# New_Project_2025-05-17_15-31-49.net
KiCad netlist of a schematic drawn in EasyEDA Pro
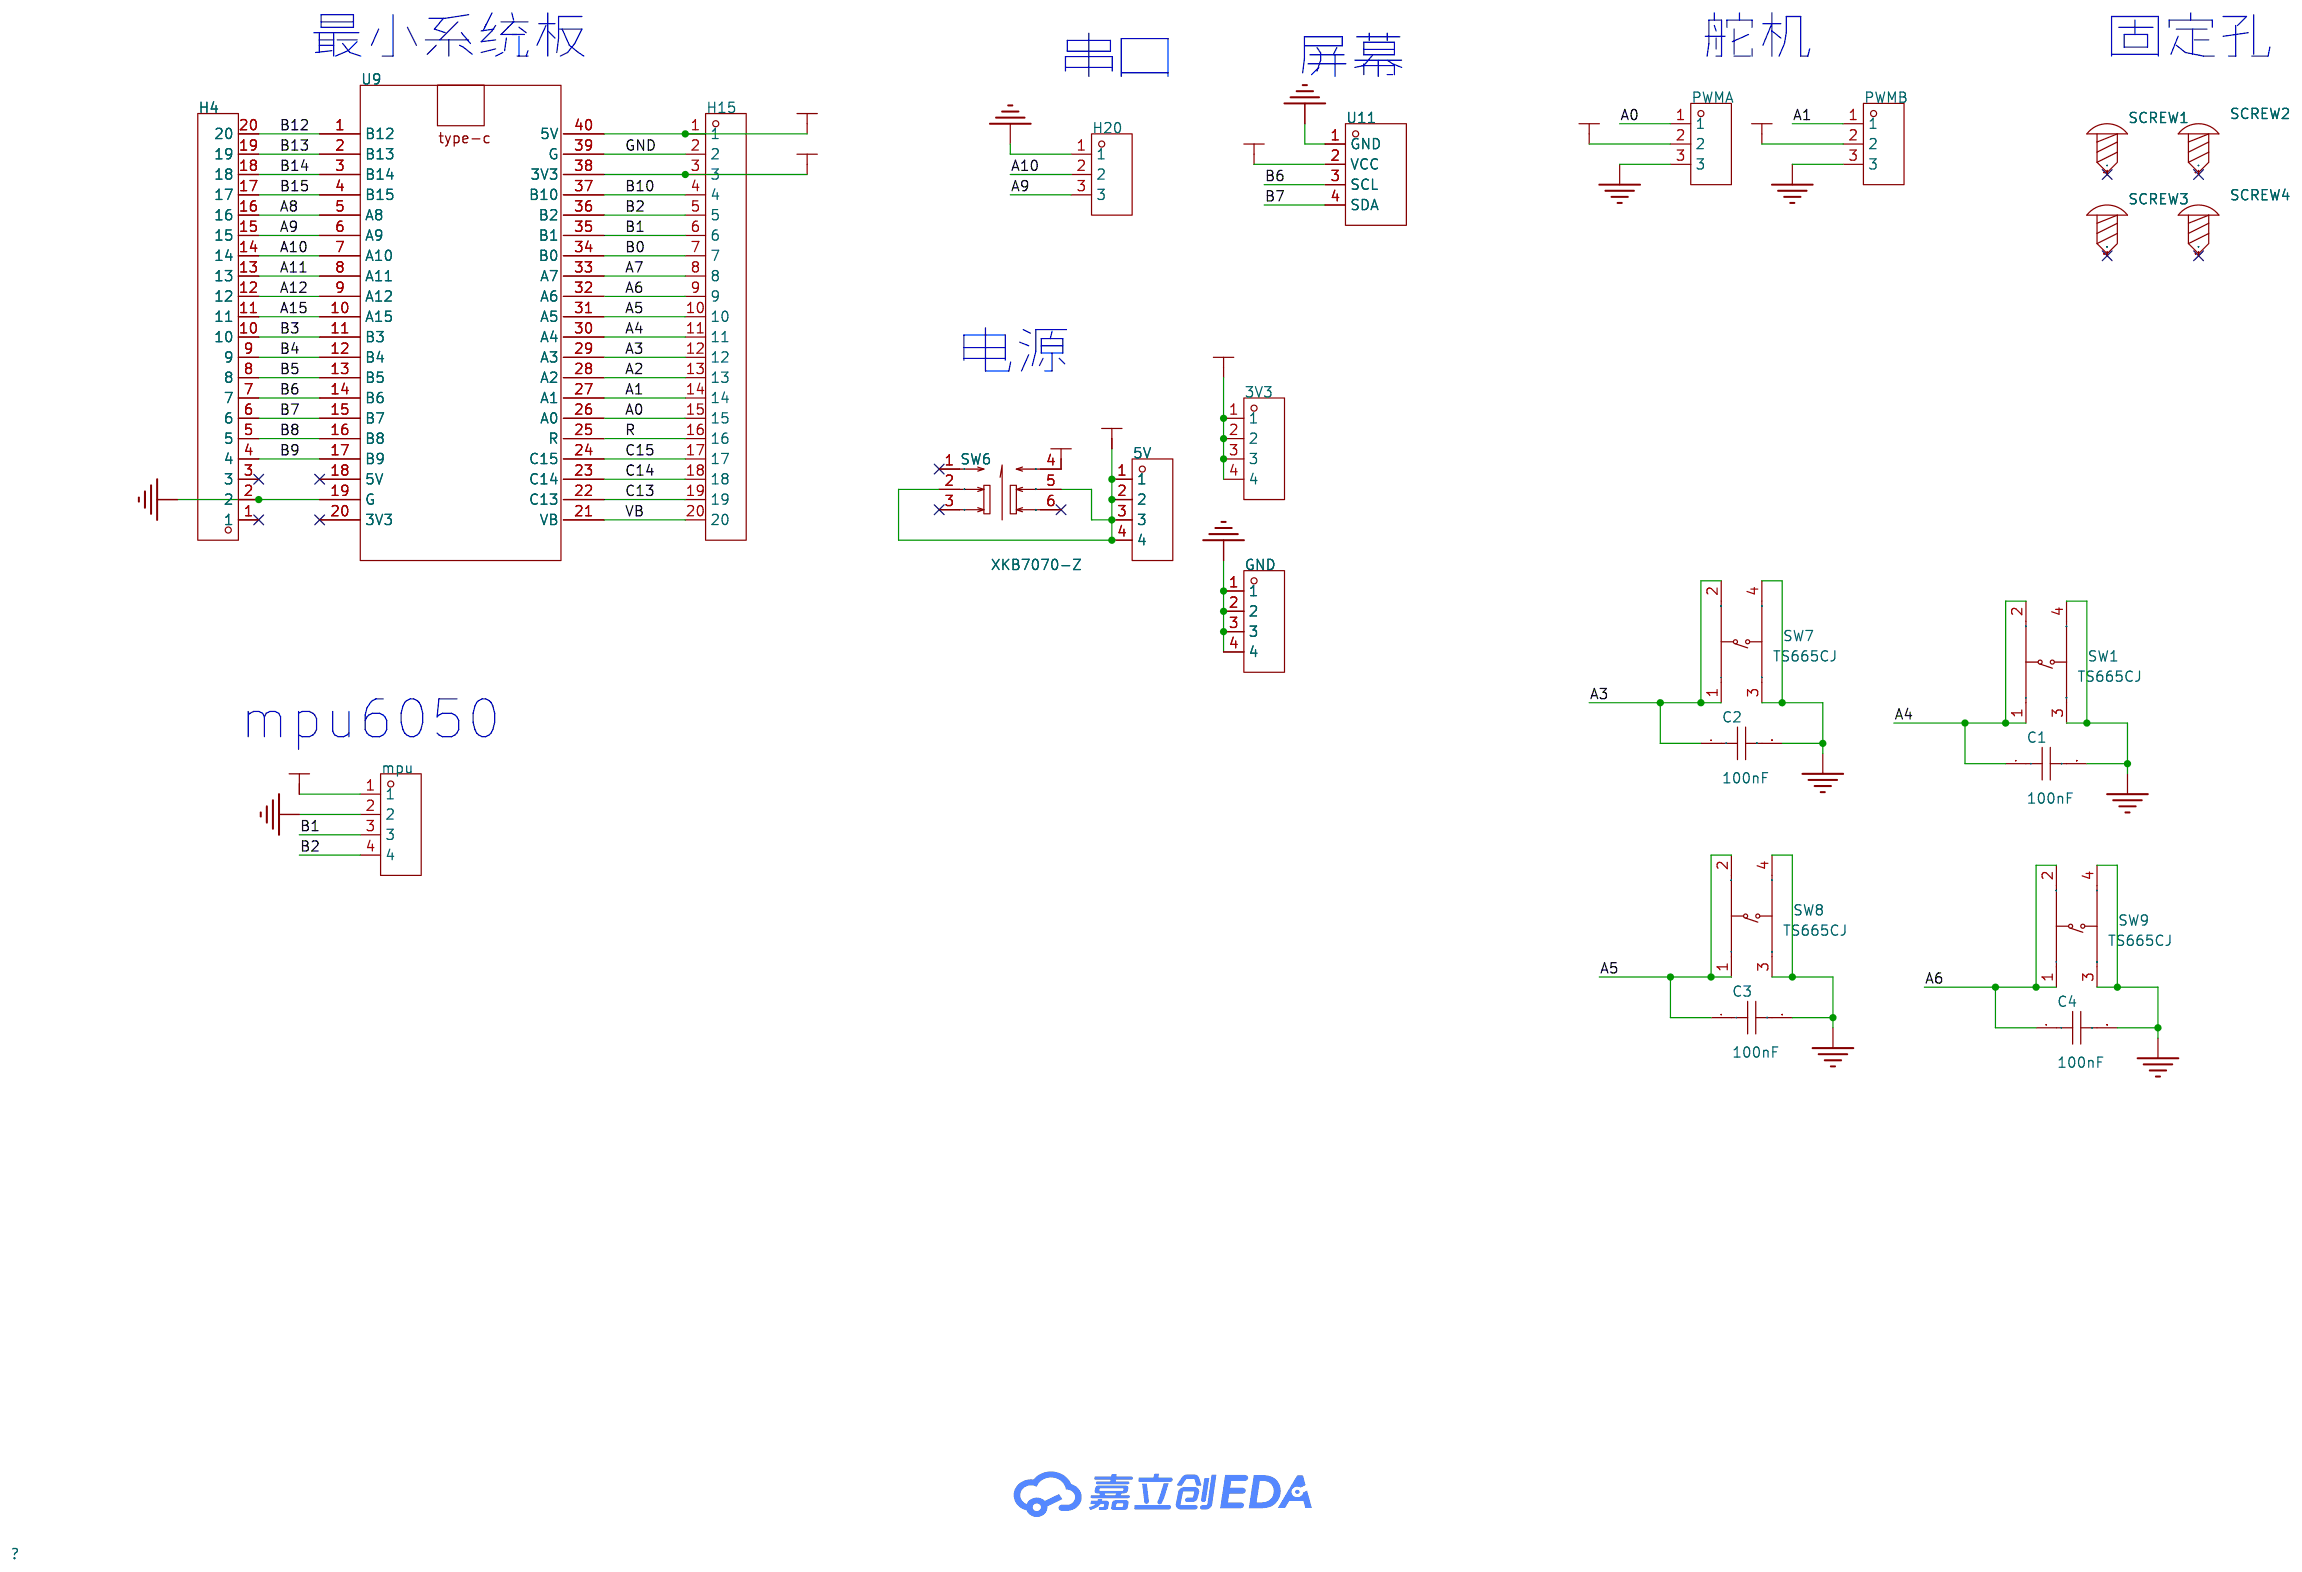
[diagram p0: schematic sheet]

(export (version "E")
  (design (tool "Eeschema 10.0.6"))
  (components
    (comp (ref "3V3")
      (value "~")
      (footprint "easyedapro:HDR-TH_4P-P2.54-V-M")
      (libsource (lib "easyedapro") (part "PZ254V-11-04P"))
    )
    (comp (ref "5V")
      (value "~")
      (footprint "easyedapro:HDR-TH_4P-P2.54-V-M")
      (libsource (lib "easyedapro") (part "PZ254V-11-04P"))
    )
    (comp (ref "C1")
      (value "100nF")
      (footprint "easyedapro:CAP-TH_L5.0-W2.5-P5.00-D1.0")
      (description "容值:100nF;精度:±20%;额定电压:50V;温度系数:Y5V;")
      (fields
        (field (name "Manufacturer Part") "CC1H104MC1FD3F6C10MF")
        (field (name "Manufacturer") "Dersonic(德尔创)")
      )
      (libsource (lib "easyedapro") (part "CC1H104MC1FD3F6C10MF"))
    )
    (comp (ref "C2")
      (value "100nF")
      (footprint "easyedapro:CAP-TH_L5.0-W2.5-P5.00-D1.0")
      (description "容值:100nF;精度:±20%;额定电压:50V;温度系数:Y5V;")
      (fields
        (field (name "Manufacturer Part") "CC1H104MC1FD3F6C10MF")
        (field (name "Manufacturer") "Dersonic(德尔创)")
      )
      (libsource (lib "easyedapro") (part "CC1H104MC1FD3F6C10MF"))
    )
    (comp (ref "C3")
      (value "100nF")
      (footprint "easyedapro:CAP-TH_L5.0-W2.5-P5.00-D1.0")
      (description "容值:100nF;精度:±20%;额定电压:50V;温度系数:Y5V;")
      (fields
        (field (name "Manufacturer Part") "CC1H104MC1FD3F6C10MF")
        (field (name "Manufacturer") "Dersonic(德尔创)")
      )
      (libsource (lib "easyedapro") (part "CC1H104MC1FD3F6C10MF"))
    )
    (comp (ref "C4")
      (value "100nF")
      (footprint "easyedapro:CAP-TH_L5.0-W2.5-P5.00-D1.0")
      (description "容值:100nF;精度:±20%;额定电压:50V;温度系数:Y5V;")
      (fields
        (field (name "Manufacturer Part") "CC1H104MC1FD3F6C10MF")
        (field (name "Manufacturer") "Dersonic(德尔创)")
      )
      (libsource (lib "easyedapro") (part "CC1H104MC1FD3F6C10MF"))
    )
    (comp (ref "GND")
      (value "~")
      (footprint "easyedapro:HDR-TH_4P-P2.54-V-M")
      (libsource (lib "easyedapro") (part "PZ254V-11-04P"))
    )
    (comp (ref "H4")
      (value "~")
      (footprint "easyedapro:HDR-TH_20P-P2.54-V-M-1")
      (libsource (lib "easyedapro") (part "HDR_2.54-1x20P"))
    )
    (comp (ref "H15")
      (value "~")
      (footprint "easyedapro:HDR-TH_20P-P2.54-V-M-1")
      (libsource (lib "easyedapro") (part "HDR_2.54-1x20P"))
    )
    (comp (ref "H20")
      (value "~")
      (footprint "easyedapro:HDR-TH_3P-P2.54-V-M")
      (libsource (lib "easyedapro") (part "PZ254V-11-03P_C2937625"))
    )
    (comp (ref "mpu")
      (value "~")
      (footprint "easyedapro:HDR-TH_4P-P2.54-V-F")
      (libsource (lib "easyedapro") (part "2.54-1*4P母"))
    )
    (comp (ref "PWMA")
      (value "~")
      (footprint "easyedapro:HDR-TH_3P-P2.54-V-M")
      (libsource (lib "easyedapro") (part "PZ254V-11-03P_C2937625"))
    )
    (comp (ref "PWMB")
      (value "~")
      (footprint "easyedapro:HDR-TH_3P-P2.54-V-M")
      (libsource (lib "easyedapro") (part "PZ254V-11-03P_C2937625"))
    )
    (comp (ref "SCREW1")
      (value "~")
      (footprint "easyedapro:M3螺丝")
      (libsource (lib "easyedapro") (part "螺丝孔"))
    )
    (comp (ref "SCREW2")
      (value "~")
      (footprint "easyedapro:M3螺丝")
      (libsource (lib "easyedapro") (part "螺丝孔"))
    )
    (comp (ref "SCREW3")
      (value "~")
      (footprint "easyedapro:M3螺丝")
      (libsource (lib "easyedapro") (part "螺丝孔"))
    )
    (comp (ref "SCREW4")
      (value "~")
      (footprint "easyedapro:M3螺丝")
      (libsource (lib "easyedapro") (part "螺丝孔"))
    )
    (comp (ref "SW1")
      (value "TS665CJ")
      (footprint "easyedapro:SW-TH_4P-L6.0-W6.0-P4.50-LS6.5")
      (description "电路结构:单刀单掷;按钮形状:圆形按钮;安装方式:直插;开关长度:6mm;开关宽度:6mm;开关高度:5mm;触点电流:50mA;额定电压(DC):12V;带灯:-;机械寿命:-;")
      (fields (field (name "Manufacturer") "SHOU HAN(首韩)"))
      (libsource (lib "easyedapro") (part "TS665CJ"))
    )
    (comp (ref "SW6")
      (value "XKB7070-Z")
      (footprint "easyedapro:SW-TH_6P-L7.0-W7.0-P2.00")
      (description "自锁/无锁:自锁;安装方式:直插;触点电流:100mA;额定电压 (AC):250V;额定电压 (DC):30V;带灯:不带;作用力:160gf;机械寿命:10万次;")
      (fields (field (name "Manufacturer") "XKB Connectivity(中国星坤)"))
      (libsource (lib "easyedapro") (part "XKB7070-Z"))
    )
    (comp (ref "SW7")
      (value "TS665CJ")
      (footprint "easyedapro:SW-TH_4P-L6.0-W6.0-P4.50-LS6.5")
      (description "电路结构:单刀单掷;按钮形状:圆形按钮;安装方式:直插;开关长度:6mm;开关宽度:6mm;开关高度:5mm;触点电流:50mA;额定电压(DC):12V;带灯:-;机械寿命:-;")
      (fields (field (name "Manufacturer") "SHOU HAN(首韩)"))
      (libsource (lib "easyedapro") (part "TS665CJ"))
    )
    (comp (ref "SW8")
      (value "TS665CJ")
      (footprint "easyedapro:SW-TH_4P-L6.0-W6.0-P4.50-LS6.5")
      (description "电路结构:单刀单掷;按钮形状:圆形按钮;安装方式:直插;开关长度:6mm;开关宽度:6mm;开关高度:5mm;触点电流:50mA;额定电压(DC):12V;带灯:-;机械寿命:-;")
      (fields (field (name "Manufacturer") "SHOU HAN(首韩)"))
      (libsource (lib "easyedapro") (part "TS665CJ"))
    )
    (comp (ref "SW9")
      (value "TS665CJ")
      (footprint "easyedapro:SW-TH_4P-L6.0-W6.0-P4.50-LS6.5")
      (description "电路结构:单刀单掷;按钮形状:圆形按钮;安装方式:直插;开关长度:6mm;开关宽度:6mm;开关高度:5mm;触点电流:50mA;额定电压(DC):12V;带灯:-;机械寿命:-;")
      (fields (field (name "Manufacturer") "SHOU HAN(首韩)"))
      (libsource (lib "easyedapro") (part "TS665CJ"))
    )
    (comp (ref "U9")
      (value "~")
      (footprint "easyedapro:F401CCU6")
      (libsource (lib "easyedapro") (part "F401CCU6"))
    )
    (comp (ref "U11")
      (value "HS96L03W2C03")
      (footprint "easyedapro:OLED-TH_L27.8-W27.2-P2.54_C9900033791")
      (description "主控芯片:SSD1315;接口类型:I2C;尺寸(inch):0.96;像素分辨率:128x64;")
      (fields (field (name "Manufacturer") "HS(汉昇)"))
      (libsource (lib "easyedapro") (part "HS96L03W2C03"))
    )
  )
  (nets
    (net (code "1") (name "/A0") (class "Default")
      (node (ref "H15") (pin "15") (pinfunction "15_15") (pintype "input"))
      (node (ref "PWMA") (pin "1") (pinfunction "1_1") (pintype "input"))
      (node (ref "U9") (pin "26") (pinfunction "A0_26") (pintype "input"))
    )
    (net (code "2") (name "/A1") (class "Default")
      (node (ref "H15") (pin "14") (pinfunction "14_14") (pintype "input"))
      (node (ref "PWMB") (pin "1") (pinfunction "1_1") (pintype "input"))
      (node (ref "U9") (pin "27") (pinfunction "A1_27") (pintype "input"))
    )
    (net (code "3") (name "/A2") (class "Default")
      (node (ref "H15") (pin "13") (pinfunction "13_13") (pintype "input"))
      (node (ref "U9") (pin "28") (pinfunction "A2_28") (pintype "input"))
    )
    (net (code "4") (name "/A3") (class "Default")
      (node (ref "C2") (pin "1") (pinfunction "1_1") (pintype "unspecified"))
      (node (ref "H15") (pin "12") (pinfunction "12_12") (pintype "input"))
      (node (ref "SW7") (pin "1") (pinfunction "A_1") (pintype "unspecified"))
      (node (ref "SW7") (pin "2") (pinfunction "B_2") (pintype "unspecified"))
      (node (ref "U9") (pin "29") (pinfunction "A3_29") (pintype "input"))
    )
    (net (code "5") (name "/A4") (class "Default")
      (node (ref "C1") (pin "1") (pinfunction "1_1") (pintype "unspecified"))
      (node (ref "H15") (pin "11") (pinfunction "11_11") (pintype "input"))
      (node (ref "SW1") (pin "1") (pinfunction "A_1") (pintype "unspecified"))
      (node (ref "SW1") (pin "2") (pinfunction "B_2") (pintype "unspecified"))
      (node (ref "U9") (pin "30") (pinfunction "A4_30") (pintype "input"))
    )
    (net (code "6") (name "/A5") (class "Default")
      (node (ref "C3") (pin "1") (pinfunction "1_1") (pintype "unspecified"))
      (node (ref "H15") (pin "10") (pinfunction "10_10") (pintype "input"))
      (node (ref "SW8") (pin "1") (pinfunction "A_1") (pintype "unspecified"))
      (node (ref "SW8") (pin "2") (pinfunction "B_2") (pintype "unspecified"))
      (node (ref "U9") (pin "31") (pinfunction "A5_31") (pintype "input"))
    )
    (net (code "7") (name "/A6") (class "Default")
      (node (ref "C4") (pin "1") (pinfunction "1_1") (pintype "unspecified"))
      (node (ref "H15") (pin "9") (pinfunction "9_9") (pintype "input"))
      (node (ref "SW9") (pin "1") (pinfunction "A_1") (pintype "unspecified"))
      (node (ref "SW9") (pin "2") (pinfunction "B_2") (pintype "unspecified"))
      (node (ref "U9") (pin "32") (pinfunction "A6_32") (pintype "input"))
    )
    (net (code "8") (name "/A7") (class "Default")
      (node (ref "H15") (pin "8") (pinfunction "8_8") (pintype "input"))
      (node (ref "U9") (pin "33") (pinfunction "A7_33") (pintype "input"))
    )
    (net (code "9") (name "/A8") (class "Default")
      (node (ref "H4") (pin "16") (pinfunction "16_16") (pintype "input"))
      (node (ref "U9") (pin "5") (pinfunction "A8_5") (pintype "input"))
    )
    (net (code "10") (name "/A9") (class "Default")
      (node (ref "H20") (pin "3") (pinfunction "3_3") (pintype "input"))
      (node (ref "H4") (pin "15") (pinfunction "15_15") (pintype "input"))
      (node (ref "U9") (pin "6") (pinfunction "A9_6") (pintype "input"))
    )
    (net (code "11") (name "/A10") (class "Default")
      (node (ref "H20") (pin "2") (pinfunction "2_2") (pintype "input"))
      (node (ref "H4") (pin "14") (pinfunction "14_14") (pintype "input"))
      (node (ref "U9") (pin "7") (pinfunction "A10_7") (pintype "input"))
    )
    (net (code "12") (name "/A11") (class "Default")
      (node (ref "H4") (pin "13") (pinfunction "13_13") (pintype "input"))
      (node (ref "U9") (pin "8") (pinfunction "A11_8") (pintype "input"))
    )
    (net (code "13") (name "/A12") (class "Default")
      (node (ref "H4") (pin "12") (pinfunction "12_12") (pintype "input"))
      (node (ref "U9") (pin "9") (pinfunction "A12_9") (pintype "input"))
    )
    (net (code "14") (name "/A15") (class "Default")
      (node (ref "H4") (pin "11") (pinfunction "11_11") (pintype "input"))
      (node (ref "U9") (pin "10") (pinfunction "A15_10") (pintype "input"))
    )
    (net (code "15") (name "/B0") (class "Default")
      (node (ref "H15") (pin "7") (pinfunction "7_7") (pintype "input"))
      (node (ref "U9") (pin "34") (pinfunction "B0_34") (pintype "input"))
    )
    (net (code "16") (name "/B1") (class "Default")
      (node (ref "H15") (pin "6") (pinfunction "6_6") (pintype "input"))
      (node (ref "U9") (pin "35") (pinfunction "B1_35") (pintype "input"))
      (node (ref "mpu") (pin "3") (pinfunction "3_3") (pintype "unspecified"))
    )
    (net (code "17") (name "/B2") (class "Default")
      (node (ref "H15") (pin "5") (pinfunction "5_5") (pintype "input"))
      (node (ref "U9") (pin "36") (pinfunction "B2_36") (pintype "input"))
      (node (ref "mpu") (pin "4") (pinfunction "4_4") (pintype "unspecified"))
    )
    (net (code "18") (name "/B3") (class "Default")
      (node (ref "H4") (pin "10") (pinfunction "10_10") (pintype "input"))
      (node (ref "U9") (pin "11") (pinfunction "B3_11") (pintype "input"))
    )
    (net (code "19") (name "/B4") (class "Default")
      (node (ref "H4") (pin "9") (pinfunction "9_9") (pintype "input"))
      (node (ref "U9") (pin "12") (pinfunction "B4_12") (pintype "input"))
    )
    (net (code "20") (name "/B5") (class "Default")
      (node (ref "H4") (pin "8") (pinfunction "8_8") (pintype "input"))
      (node (ref "U9") (pin "13") (pinfunction "B5_13") (pintype "input"))
    )
    (net (code "21") (name "/B6") (class "Default")
      (node (ref "H4") (pin "7") (pinfunction "7_7") (pintype "input"))
      (node (ref "U11") (pin "3") (pinfunction "SCL_3") (pintype "unspecified"))
      (node (ref "U9") (pin "14") (pinfunction "B6_14") (pintype "input"))
    )
    (net (code "22") (name "/B7") (class "Default")
      (node (ref "H4") (pin "6") (pinfunction "6_6") (pintype "input"))
      (node (ref "U11") (pin "4") (pinfunction "SDA_4") (pintype "unspecified"))
      (node (ref "U9") (pin "15") (pinfunction "B7_15") (pintype "input"))
    )
    (net (code "23") (name "/B8") (class "Default")
      (node (ref "H4") (pin "5") (pinfunction "5_5") (pintype "input"))
      (node (ref "U9") (pin "16") (pinfunction "B8_16") (pintype "input"))
    )
    (net (code "24") (name "/B9") (class "Default")
      (node (ref "H4") (pin "4") (pinfunction "4_4") (pintype "input"))
      (node (ref "U9") (pin "17") (pinfunction "B9_17") (pintype "input"))
    )
    (net (code "25") (name "/B10") (class "Default")
      (node (ref "H15") (pin "4") (pinfunction "4_4") (pintype "input"))
      (node (ref "U9") (pin "37") (pinfunction "B10_37") (pintype "input"))
    )
    (net (code "26") (name "/B12") (class "Default")
      (node (ref "H4") (pin "20") (pinfunction "20_20") (pintype "input"))
      (node (ref "U9") (pin "1") (pinfunction "B12_1") (pintype "input"))
    )
    (net (code "27") (name "/B13") (class "Default")
      (node (ref "H4") (pin "19") (pinfunction "19_19") (pintype "input"))
      (node (ref "U9") (pin "2") (pinfunction "B13_2") (pintype "input"))
    )
    (net (code "28") (name "/B14") (class "Default")
      (node (ref "H4") (pin "18") (pinfunction "18_18") (pintype "input"))
      (node (ref "U9") (pin "3") (pinfunction "B14_3") (pintype "input"))
    )
    (net (code "29") (name "/B15") (class "Default")
      (node (ref "H4") (pin "17") (pinfunction "17_17") (pintype "input"))
      (node (ref "U9") (pin "4") (pinfunction "B15_4") (pintype "input"))
    )
    (net (code "30") (name "/C13") (class "Default")
      (node (ref "H15") (pin "19") (pinfunction "19_19") (pintype "input"))
      (node (ref "U9") (pin "22") (pinfunction "C13_22") (pintype "input"))
    )
    (net (code "31") (name "/C14") (class "Default")
      (node (ref "H15") (pin "18") (pinfunction "18_18") (pintype "input"))
      (node (ref "U9") (pin "23") (pinfunction "C14_23") (pintype "input"))
    )
    (net (code "32") (name "/C15") (class "Default")
      (node (ref "H15") (pin "17") (pinfunction "17_17") (pintype "input"))
      (node (ref "U9") (pin "24") (pinfunction "C15_24") (pintype "input"))
    )
    (net (code "33") (name "/R") (class "Default")
      (node (ref "H15") (pin "16") (pinfunction "16_16") (pintype "input"))
      (node (ref "U9") (pin "25") (pinfunction "R_25") (pintype "input"))
    )
    (net (code "34") (name "/VB") (class "Default")
      (node (ref "H15") (pin "20") (pinfunction "20_20") (pintype "input"))
      (node (ref "U9") (pin "21") (pinfunction "VB_21") (pintype "input"))
    )
    (net (code "35") (name "3V3") (class "Default")
      (node (ref "3V3") (pin "1") (pinfunction "1_1") (pintype "unspecified"))
      (node (ref "3V3") (pin "2") (pinfunction "2_2") (pintype "unspecified"))
      (node (ref "3V3") (pin "3") (pinfunction "3_3") (pintype "unspecified"))
      (node (ref "3V3") (pin "4") (pinfunction "4_4") (pintype "unspecified"))
      (node (ref "H15") (pin "3") (pinfunction "3_3") (pintype "input"))
      (node (ref "U11") (pin "2") (pinfunction "VCC_2") (pintype "unspecified"))
      (node (ref "U9") (pin "38") (pinfunction "3V3_38") (pintype "input"))
    )
    (net (code "36") (name "5V") (class "Default")
      (node (ref "5V") (pin "1") (pinfunction "1_1") (pintype "unspecified"))
      (node (ref "5V") (pin "2") (pinfunction "2_2") (pintype "unspecified"))
      (node (ref "5V") (pin "3") (pinfunction "3_3") (pintype "unspecified"))
      (node (ref "5V") (pin "4") (pinfunction "4_4") (pintype "unspecified"))
      (node (ref "H15") (pin "1") (pinfunction "1_1") (pintype "input"))
      (node (ref "PWMA") (pin "2") (pinfunction "2_2") (pintype "input"))
      (node (ref "PWMB") (pin "2") (pinfunction "2_2") (pintype "input"))
      (node (ref "SW6") (pin "2") (pinfunction "2_2") (pintype "unspecified"))
      (node (ref "SW6") (pin "4") (pinfunction "4_4") (pintype "unspecified"))
      (node (ref "SW6") (pin "5") (pinfunction "5_5") (pintype "unspecified"))
      (node (ref "U9") (pin "40") (pinfunction "5V_40") (pintype "input"))
      (node (ref "mpu") (pin "1") (pinfunction "1_1") (pintype "unspecified"))
    )
    (net (code "37") (name "GND") (class "Default")
      (node (ref "C1") (pin "2") (pinfunction "2_2") (pintype "unspecified"))
      (node (ref "C2") (pin "2") (pinfunction "2_2") (pintype "unspecified"))
      (node (ref "C3") (pin "2") (pinfunction "2_2") (pintype "unspecified"))
      (node (ref "C4") (pin "2") (pinfunction "2_2") (pintype "unspecified"))
      (node (ref "GND") (pin "1") (pinfunction "1_1") (pintype "unspecified"))
      (node (ref "GND") (pin "2") (pinfunction "2_2") (pintype "unspecified"))
      (node (ref "GND") (pin "3") (pinfunction "3_3") (pintype "unspecified"))
      (node (ref "GND") (pin "4") (pinfunction "4_4") (pintype "unspecified"))
      (node (ref "H15") (pin "2") (pinfunction "2_2") (pintype "input"))
      (node (ref "H20") (pin "1") (pinfunction "1_1") (pintype "input"))
      (node (ref "H4") (pin "2") (pinfunction "2_2") (pintype "input"))
      (node (ref "PWMA") (pin "3") (pinfunction "3_3") (pintype "input"))
      (node (ref "PWMB") (pin "3") (pinfunction "3_3") (pintype "input"))
      (node (ref "SW1") (pin "3") (pinfunction "C_3") (pintype "unspecified"))
      (node (ref "SW1") (pin "4") (pinfunction "D_4") (pintype "unspecified"))
      (node (ref "SW7") (pin "3") (pinfunction "C_3") (pintype "unspecified"))
      (node (ref "SW7") (pin "4") (pinfunction "D_4") (pintype "unspecified"))
      (node (ref "SW8") (pin "3") (pinfunction "C_3") (pintype "unspecified"))
      (node (ref "SW8") (pin "4") (pinfunction "D_4") (pintype "unspecified"))
      (node (ref "SW9") (pin "3") (pinfunction "C_3") (pintype "unspecified"))
      (node (ref "SW9") (pin "4") (pinfunction "D_4") (pintype "unspecified"))
      (node (ref "U11") (pin "1") (pinfunction "GND_1") (pintype "unspecified"))
      (node (ref "U9") (pin "19") (pinfunction "G_19") (pintype "input"))
      (node (ref "U9") (pin "39") (pinfunction "G_39") (pintype "input"))
      (node (ref "mpu") (pin "2") (pinfunction "2_2") (pintype "unspecified"))
    )
    (net (code "38") (name "unconnected-(H4-Pad1)") (class "Default")
      (node (ref "H4") (pin "1") (pinfunction "1_1") (pintype "input+no_connect"))
    )
    (net (code "39") (name "unconnected-(H4-Pad3)") (class "Default")
      (node (ref "H4") (pin "3") (pinfunction "3_3") (pintype "input+no_connect"))
    )
    (net (code "40") (name "unconnected-(SCREW1-Pad1)") (class "Default")
      (node (ref "SCREW1") (pin "1") (pinfunction "1_1") (pintype "input+no_connect"))
    )
    (net (code "41") (name "unconnected-(SCREW2-Pad1)") (class "Default")
      (node (ref "SCREW2") (pin "1") (pinfunction "1_1") (pintype "input+no_connect"))
    )
    (net (code "42") (name "unconnected-(SCREW3-Pad1)") (class "Default")
      (node (ref "SCREW3") (pin "1") (pinfunction "1_1") (pintype "input+no_connect"))
    )
    (net (code "43") (name "unconnected-(SCREW4-Pad1)") (class "Default")
      (node (ref "SCREW4") (pin "1") (pinfunction "1_1") (pintype "input+no_connect"))
    )
    (net (code "44") (name "unconnected-(SW6-Pad1)") (class "Default")
      (node (ref "SW6") (pin "1") (pinfunction "1_1") (pintype "unspecified+no_connect"))
    )
    (net (code "45") (name "unconnected-(SW6-Pad3)") (class "Default")
      (node (ref "SW6") (pin "3") (pinfunction "3_3") (pintype "unspecified+no_connect"))
    )
    (net (code "46") (name "unconnected-(SW6-Pad6)") (class "Default")
      (node (ref "SW6") (pin "6") (pinfunction "6_6") (pintype "unspecified+no_connect"))
    )
    (net (code "47") (name "unconnected-(U9-3V3-Pad20)") (class "Default")
      (node (ref "U9") (pin "20") (pinfunction "3V3_20") (pintype "input+no_connect"))
    )
    (net (code "48") (name "unconnected-(U9-5V-Pad18)") (class "Default")
      (node (ref "U9") (pin "18") (pinfunction "5V_18") (pintype "input+no_connect"))
    )
  )
)
